# ATTinyServo_v12.net
KiCad netlist of a schematic drawn in EAGLE
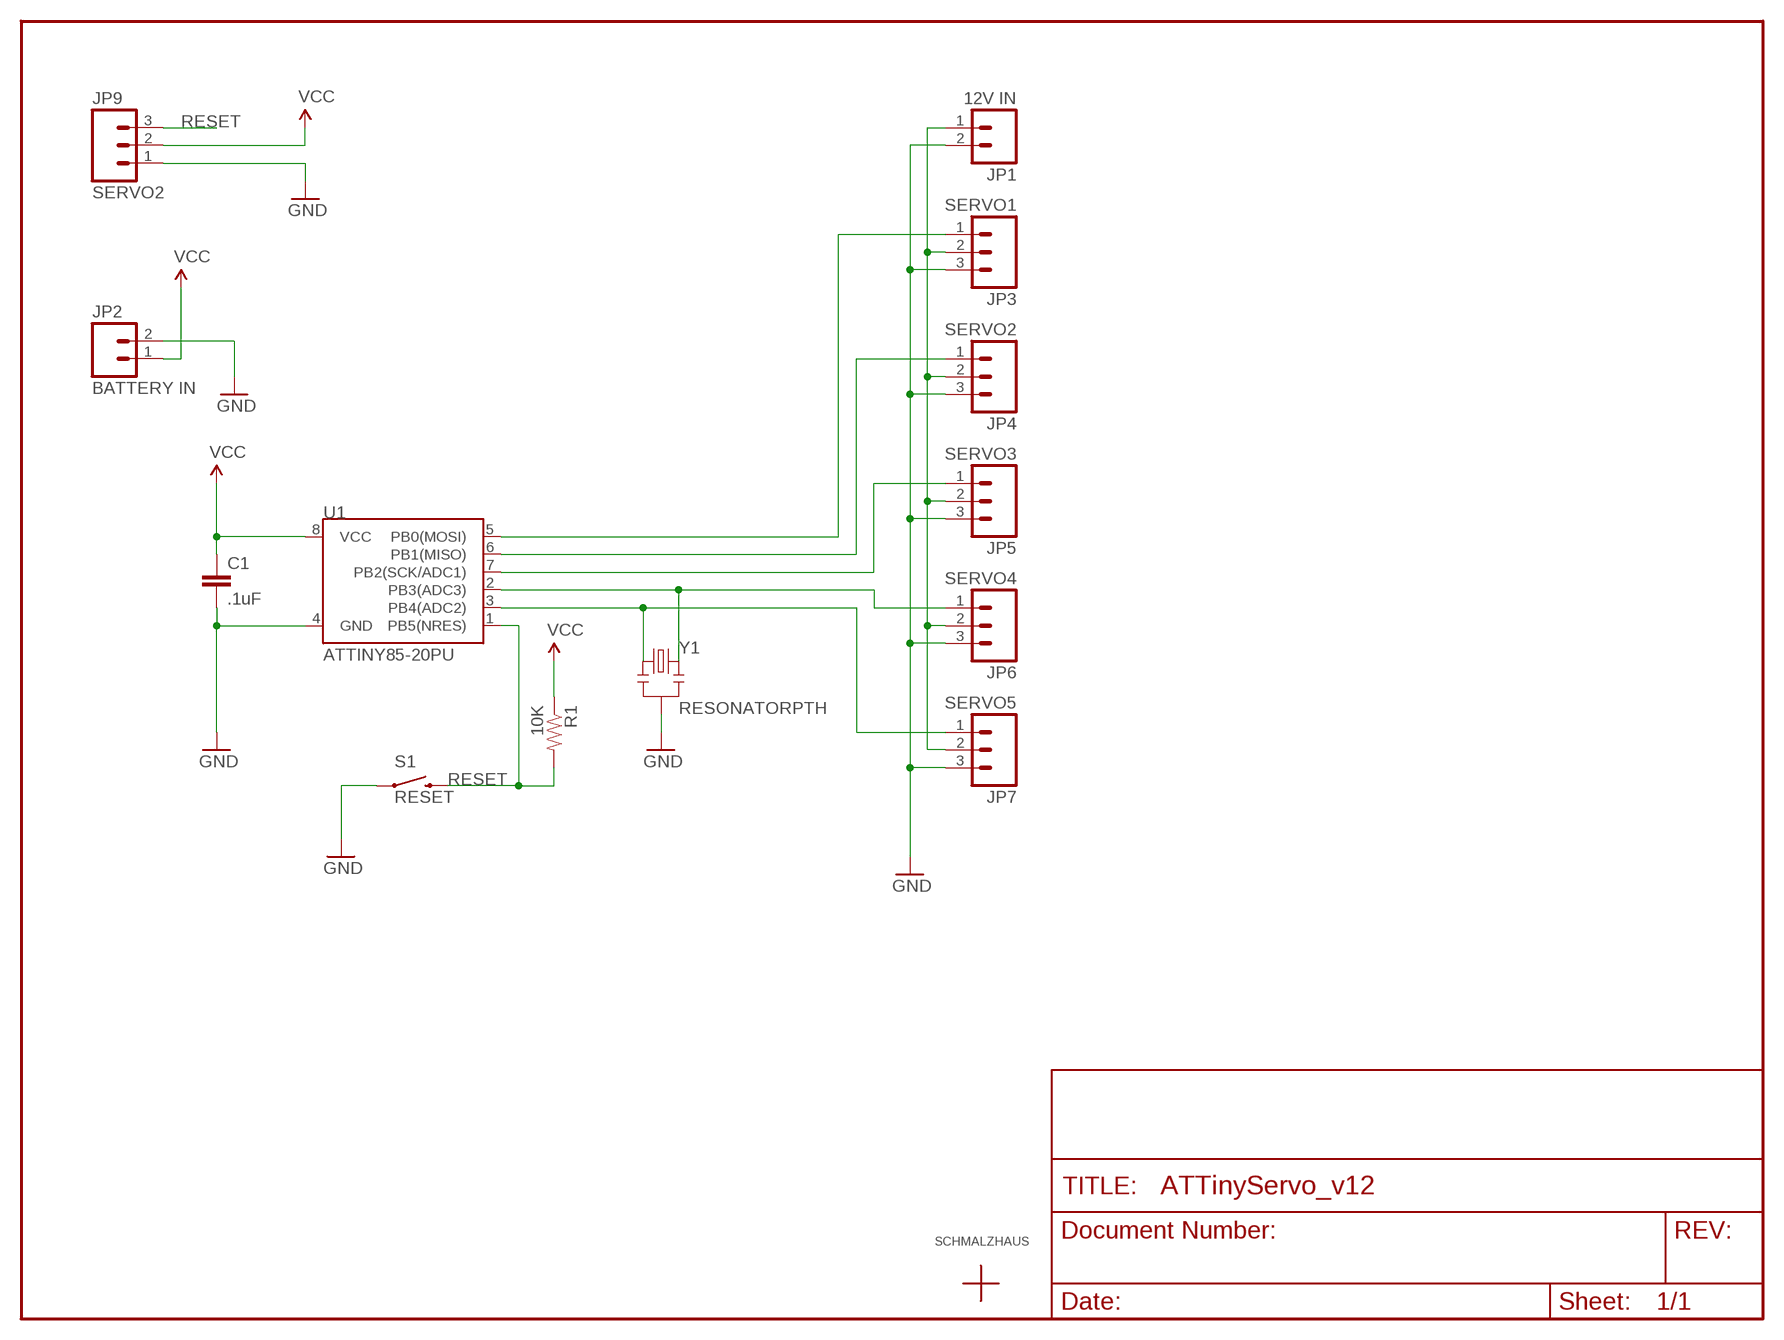
[diagram p0: schematic, sheet 1]

(export (version "E")
  (design (tool "Eeschema 10.0.6"))
  (components
    (comp (ref "C1")
      (value ".1uF")
      (footprint "eagle-import:CAP-PTH-SMALL-KIT")
      (libsource (lib "eagle-import") (part "CAPKIT"))
    )
    (comp (ref "JP1")
      (value "12V IN")
      (footprint "eagle-import:SCREWTERMINAL-3.5MM-2")
      (libsource (lib "eagle-import") (part "M023.5MM"))
    )
    (comp (ref "JP2")
      (value "BATTERY IN")
      (footprint "eagle-import:SCREWTERMINAL-3.5MM-2")
      (libsource (lib "eagle-import") (part "M023.5MM"))
    )
    (comp (ref "JP3")
      (value "SERVO1")
      (footprint "eagle-import:1X03")
      (libsource (lib "eagle-import") (part "M03PTH"))
    )
    (comp (ref "JP4")
      (value "SERVO2")
      (footprint "eagle-import:1X03")
      (libsource (lib "eagle-import") (part "M03PTH"))
    )
    (comp (ref "JP5")
      (value "SERVO3")
      (footprint "eagle-import:1X03")
      (libsource (lib "eagle-import") (part "M03PTH"))
    )
    (comp (ref "JP6")
      (value "SERVO4")
      (footprint "eagle-import:1X03")
      (libsource (lib "eagle-import") (part "M03PTH"))
    )
    (comp (ref "JP7")
      (value "SERVO5")
      (footprint "eagle-import:1X03")
      (libsource (lib "eagle-import") (part "M03PTH"))
    )
    (comp (ref "JP9")
      (value "SERVO2")
      (footprint "eagle-import:1X03")
      (libsource (lib "eagle-import") (part "M03PTH"))
    )
    (comp (ref "R1")
      (value "10K")
      (footprint "eagle-import:AXIAL-0.4")
      (libsource (lib "eagle-import") (part "RESISTORPTH-1/4W"))
    )
    (comp (ref "S1")
      (value "RESET")
      (footprint "eagle-import:TACTILE-PTH")
      (libsource (lib "eagle-import") (part "SWITCH-MOMENTARY-2PTH"))
    )
    (comp (ref "U$1")
      (value "SCHMALZHAUSSCHMALZHAUS_SMALL")
      (footprint "eagle-import:SCHMALZHAUS_SMALL")
      (libsource (lib "eagle-import") (part "SCHMALZHAUSSCHMALZHAUS_SMALL"))
    )
    (comp (ref "U1")
      (value "ATTINY85-20PU")
      (footprint "eagle-import:DIP08")
      (libsource (lib "eagle-import") (part "ATTINY45DIP8"))
    )
    (comp (ref "Y1")
      (value "RESONATORPTH")
      (footprint "eagle-import:RESONATOR-PTH")
      (libsource (lib "eagle-import") (part "RESONATORPTH"))
    )
  )
  (nets
    (net (code "1") (name "/RESET") (class "Default")
      (node (ref "JP9") (pin "3") (pinfunction "3_3") (pintype "passive"))
      (node (ref "R1") (pin "P$2") (pinfunction "2_P$2") (pintype "passive"))
      (node (ref "S1") (pin "3") (pinfunction "2_3") (pintype "passive"))
      (node (ref "U1") (pin "1") (pinfunction "PB5(NRES)_1") (pintype "bidirectional"))
    )
    (net (code "2") (name "GND") (class "Default")
      (node (ref "C1") (pin "2") (pinfunction "2_2") (pintype "passive"))
      (node (ref "JP1") (pin "2") (pinfunction "2_2") (pintype "passive"))
      (node (ref "JP2") (pin "2") (pinfunction "2_2") (pintype "passive"))
      (node (ref "JP3") (pin "3") (pinfunction "3_3") (pintype "passive"))
      (node (ref "JP4") (pin "3") (pinfunction "3_3") (pintype "passive"))
      (node (ref "JP5") (pin "3") (pinfunction "3_3") (pintype "passive"))
      (node (ref "JP6") (pin "3") (pinfunction "3_3") (pintype "passive"))
      (node (ref "JP7") (pin "3") (pinfunction "3_3") (pintype "passive"))
      (node (ref "JP9") (pin "1") (pinfunction "1_1") (pintype "passive"))
      (node (ref "S1") (pin "1") (pinfunction "1_1") (pintype "passive"))
      (node (ref "U1") (pin "4") (pinfunction "GND_4") (pintype "bidirectional"))
      (node (ref "Y1") (pin "2") (pinfunction "2_2") (pintype "passive"))
    )
    (net (code "3") (name "Net-(JP1-Pad1)") (class "Default")
      (node (ref "JP1") (pin "1") (pinfunction "1_1") (pintype "passive"))
      (node (ref "JP3") (pin "2") (pinfunction "2_2") (pintype "passive"))
      (node (ref "JP4") (pin "2") (pinfunction "2_2") (pintype "passive"))
      (node (ref "JP5") (pin "2") (pinfunction "2_2") (pintype "passive"))
      (node (ref "JP6") (pin "2") (pinfunction "2_2") (pintype "passive"))
      (node (ref "JP7") (pin "2") (pinfunction "2_2") (pintype "passive"))
    )
    (net (code "4") (name "Net-(U1-PB0(MOSI))") (class "Default")
      (node (ref "JP3") (pin "1") (pinfunction "1_1") (pintype "passive"))
      (node (ref "U1") (pin "5") (pinfunction "PB0(MOSI)_5") (pintype "bidirectional"))
    )
    (net (code "5") (name "Net-(U1-PB1(MISO))") (class "Default")
      (node (ref "JP4") (pin "1") (pinfunction "1_1") (pintype "passive"))
      (node (ref "U1") (pin "6") (pinfunction "PB1(MISO)_6") (pintype "bidirectional"))
    )
    (net (code "6") (name "Net-(U1-PB2(SCK{slash}ADC1))") (class "Default")
      (node (ref "JP5") (pin "1") (pinfunction "1_1") (pintype "passive"))
      (node (ref "U1") (pin "7") (pinfunction "PB2(SCK/ADC1)_7") (pintype "bidirectional"))
    )
    (net (code "7") (name "Net-(U1-PB3(ADC3))") (class "Default")
      (node (ref "JP6") (pin "1") (pinfunction "1_1") (pintype "passive"))
      (node (ref "U1") (pin "2") (pinfunction "PB3(ADC3)_2") (pintype "bidirectional"))
      (node (ref "Y1") (pin "3") (pinfunction "3_3") (pintype "passive"))
    )
    (net (code "8") (name "Net-(U1-PB4(ADC2))") (class "Default")
      (node (ref "JP7") (pin "1") (pinfunction "1_1") (pintype "passive"))
      (node (ref "U1") (pin "3") (pinfunction "PB4(ADC2)_3") (pintype "bidirectional"))
      (node (ref "Y1") (pin "1") (pinfunction "1_1") (pintype "passive"))
    )
    (net (code "9") (name "VCC") (class "Default")
      (node (ref "C1") (pin "1") (pinfunction "1_1") (pintype "passive"))
      (node (ref "JP2") (pin "1") (pinfunction "1_1") (pintype "passive"))
      (node (ref "JP9") (pin "2") (pinfunction "2_2") (pintype "passive"))
      (node (ref "R1") (pin "P$1") (pinfunction "1_P$1") (pintype "passive"))
      (node (ref "U1") (pin "8") (pinfunction "VCC_8") (pintype "bidirectional"))
    )
  )
)
